# IdealDiode.net
KiCad netlist of a schematic drawn in Altium Designer
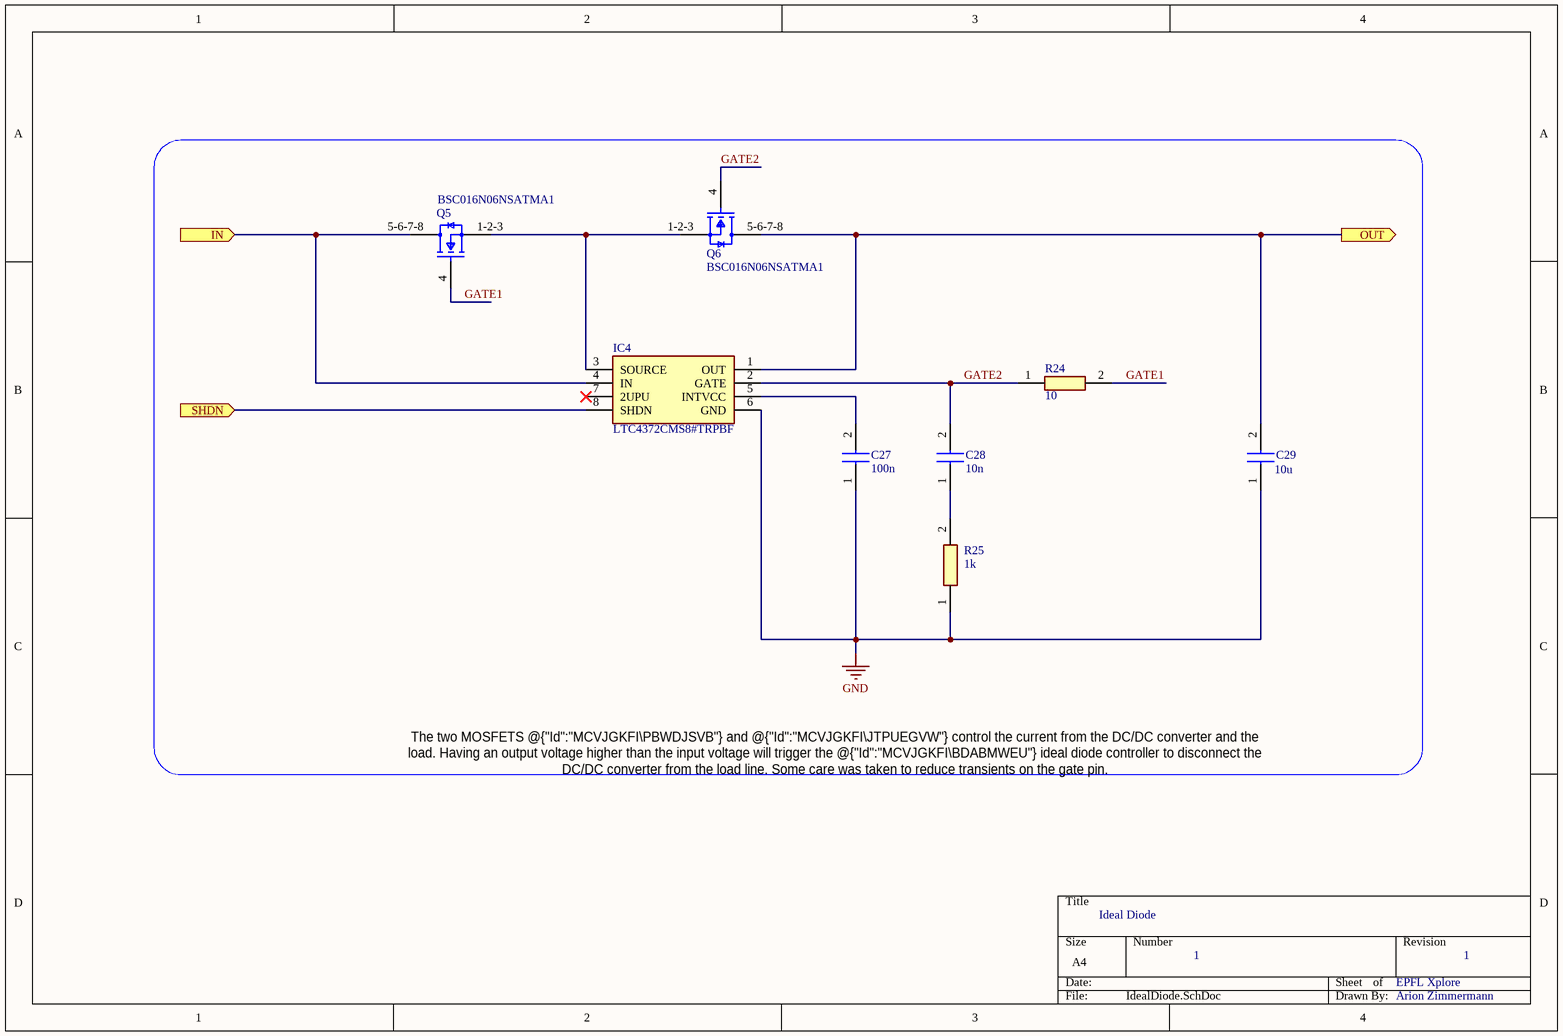
[diagram p0: IdealDiode.SchDoc]

(export (version "E")
  (design (tool "Eeschema 10.0.6"))
  (components
    (comp (ref "C27")
      (value "100n")
      (footprint "CAPC1608X95N")
      (description "Capacitor")
      (fields
        (field (name "MANUFACTURER_PART_NUMBER") "C0603C104K5RACTU")
        (field (name "MOUSER PART NUMBER") "80-C0603C104K5R")
      )
      (libsource (lib "*") (part "C0603C104K5RACTU"))
    )
    (comp (ref "C28")
      (value "10n")
      (footprint "CAPC1608X95N")
      (description "Capacitor")
      (fields
        (field (name "MANUFACTURER_PART_NUMBER") "C0603C104K5RACTU")
        (field (name "MOUSER PART NUMBER") "80-C0603C104K5R")
      )
      (libsource (lib "*") (part "C0603C104K5RACTU"))
    )
    (comp (ref "C29")
      (value "10u")
      (footprint "CAPC3225X230N")
      (description "Capacitor")
      (fields
        (field (name "MANUFACTURER_PART_NUMBER") "C3225X7R2A106K250AC")
        (field (name "MOUSER PART NUMBER") "810-C3225X7R2A106K25")
      )
      (libsource (lib "SamacSys") (part "C3225X7R2A106K250AC"))
    )
    (comp (ref "IC4")
      (value "LTC4372CMS8#TRPBF")
      (footprint "SOP65P490X110-8N")
      (description "Integrated Circuit")
      (fields (field (name "MOUSER PART NUMBER") "584-LTC4372CMS8TRPBF"))
      (libsource (lib "*") (part "LTC4372CMS8#TRPBF"))
    )
    (comp (ref "Q5")
      (value "BSC016N06NSATMA1")
      (footprint "FP-PG-TDSON-8-MFG")
      (description "MOSFET N-CH 60V 30A TDSON-8")
      (fields
        (field (name "OCTOPART") "https://octopart.com/bsc016n06nsatma1-infineon-23421881")
        (field (name "MANUFACTURER") "Infineon")
      )
      (libsource (lib "Altium Content Vault") (part "1b0cff3a23bd3632373e77d40b07099"))
    )
    (comp (ref "Q6")
      (value "BSC016N06NSATMA1")
      (footprint "FP-PG-TDSON-8-MFG")
      (description "MOSFET N-CH 60V 30A TDSON-8")
      (fields
        (field (name "OCTOPART") "https://octopart.com/bsc016n06nsatma1-infineon-23421881")
        (field (name "MANUFACTURER") "Infineon")
      )
      (libsource (lib "Altium Content Vault") (part "1b0cff3a23bd3632373e77d40b07099"))
    )
    (comp (ref "R24")
      (value "10")
      (footprint "RESC1608X55N")
      (description "Resistor")
      (fields
        (field (name "MANUFACTURER_PART_NUMBER") "CRCW0603100RFKEBC")
        (field (name "MOUSER PART NUMBER") "71-CRCW0603100RFKEBC")
      )
      (libsource (lib "*") (part "CRCW0603100RFKEBC"))
    )
    (comp (ref "R25")
      (value "1k")
      (footprint "RESC1608X55N")
      (description "Resistor")
      (fields
        (field (name "MANUFACTURER_PART_NUMBER") "CRCW0603100RFKEBC")
        (field (name "MOUSER PART NUMBER") "71-CRCW0603100RFKEBC")
      )
      (libsource (lib "") (part "CRCW0603100RFKEBC_1"))
    )
  )
  (nets
    (net (code "1") (name "/GATE1") (class "Default")
      (node (ref "Q5") (pin "4") (pinfunction "G_4") (pintype "passive"))
      (node (ref "R24") (pin "2") (pinfunction "2_2") (pintype "passive"))
    )
    (net (code "2") (name "/GATE2") (class "Default")
      (node (ref "C28") (pin "2") (pinfunction "2_2") (pintype "passive"))
      (node (ref "IC4") (pin "2") (pinfunction "GATE_2") (pintype "passive"))
      (node (ref "Q6") (pin "4") (pinfunction "G_4") (pintype "passive"))
      (node (ref "R24") (pin "1") (pinfunction "1_1") (pintype "passive"))
    )
    (net (code "3") (name "/IN") (class "Default")
      (node (ref "IC4") (pin "4") (pinfunction "IN_4") (pintype "passive"))
      (node (ref "Q5") (pin "5-6-7-8") (pinfunction "D_5-6-7-8") (pintype "passive"))
    )
    (net (code "4") (name "/OUT") (class "Default")
      (node (ref "C29") (pin "2") (pinfunction "2_2") (pintype "passive"))
      (node (ref "IC4") (pin "1") (pinfunction "OUT_1") (pintype "passive"))
      (node (ref "Q6") (pin "5-6-7-8") (pinfunction "D_5-6-7-8") (pintype "passive"))
    )
    (net (code "5") (name "/SHDN") (class "Default")
      (node (ref "IC4") (pin "8") (pinfunction "SHDN_8") (pintype "passive"))
    )
    (net (code "6") (name "GND") (class "Default")
      (node (ref "C27") (pin "1") (pinfunction "1_1") (pintype "passive"))
      (node (ref "C29") (pin "1") (pinfunction "1_1") (pintype "passive"))
      (node (ref "IC4") (pin "6") (pinfunction "GND_6") (pintype "passive"))
      (node (ref "R25") (pin "1") (pinfunction "1_1") (pintype "passive"))
    )
    (net (code "7") (name "Net-(C28-Pad1)") (class "Default")
      (node (ref "C28") (pin "1") (pinfunction "1_1") (pintype "passive"))
      (node (ref "R25") (pin "2") (pinfunction "2_2") (pintype "passive"))
    )
    (net (code "8") (name "Net-(IC4-INTVCC)") (class "Default")
      (node (ref "C27") (pin "2") (pinfunction "2_2") (pintype "passive"))
      (node (ref "IC4") (pin "5") (pinfunction "INTVCC_5") (pintype "passive"))
    )
    (net (code "9") (name "Net-(IC4-SOURCE)") (class "Default")
      (node (ref "IC4") (pin "3") (pinfunction "SOURCE_3") (pintype "passive"))
      (node (ref "Q5") (pin "1-2-3") (pinfunction "S_1-2-3") (pintype "passive"))
      (node (ref "Q6") (pin "1-2-3") (pinfunction "S_1-2-3") (pintype "passive"))
    )
    (net (code "10") (name "unconnected-(IC4-2UPU-Pad7)") (class "Default")
      (node (ref "IC4") (pin "7") (pinfunction "2UPU_7") (pintype "passive+no_connect"))
    )
  )
)
